# gk_midi_board_v2_5.net
KiCad netlist of a schematic drawn in EAGLE
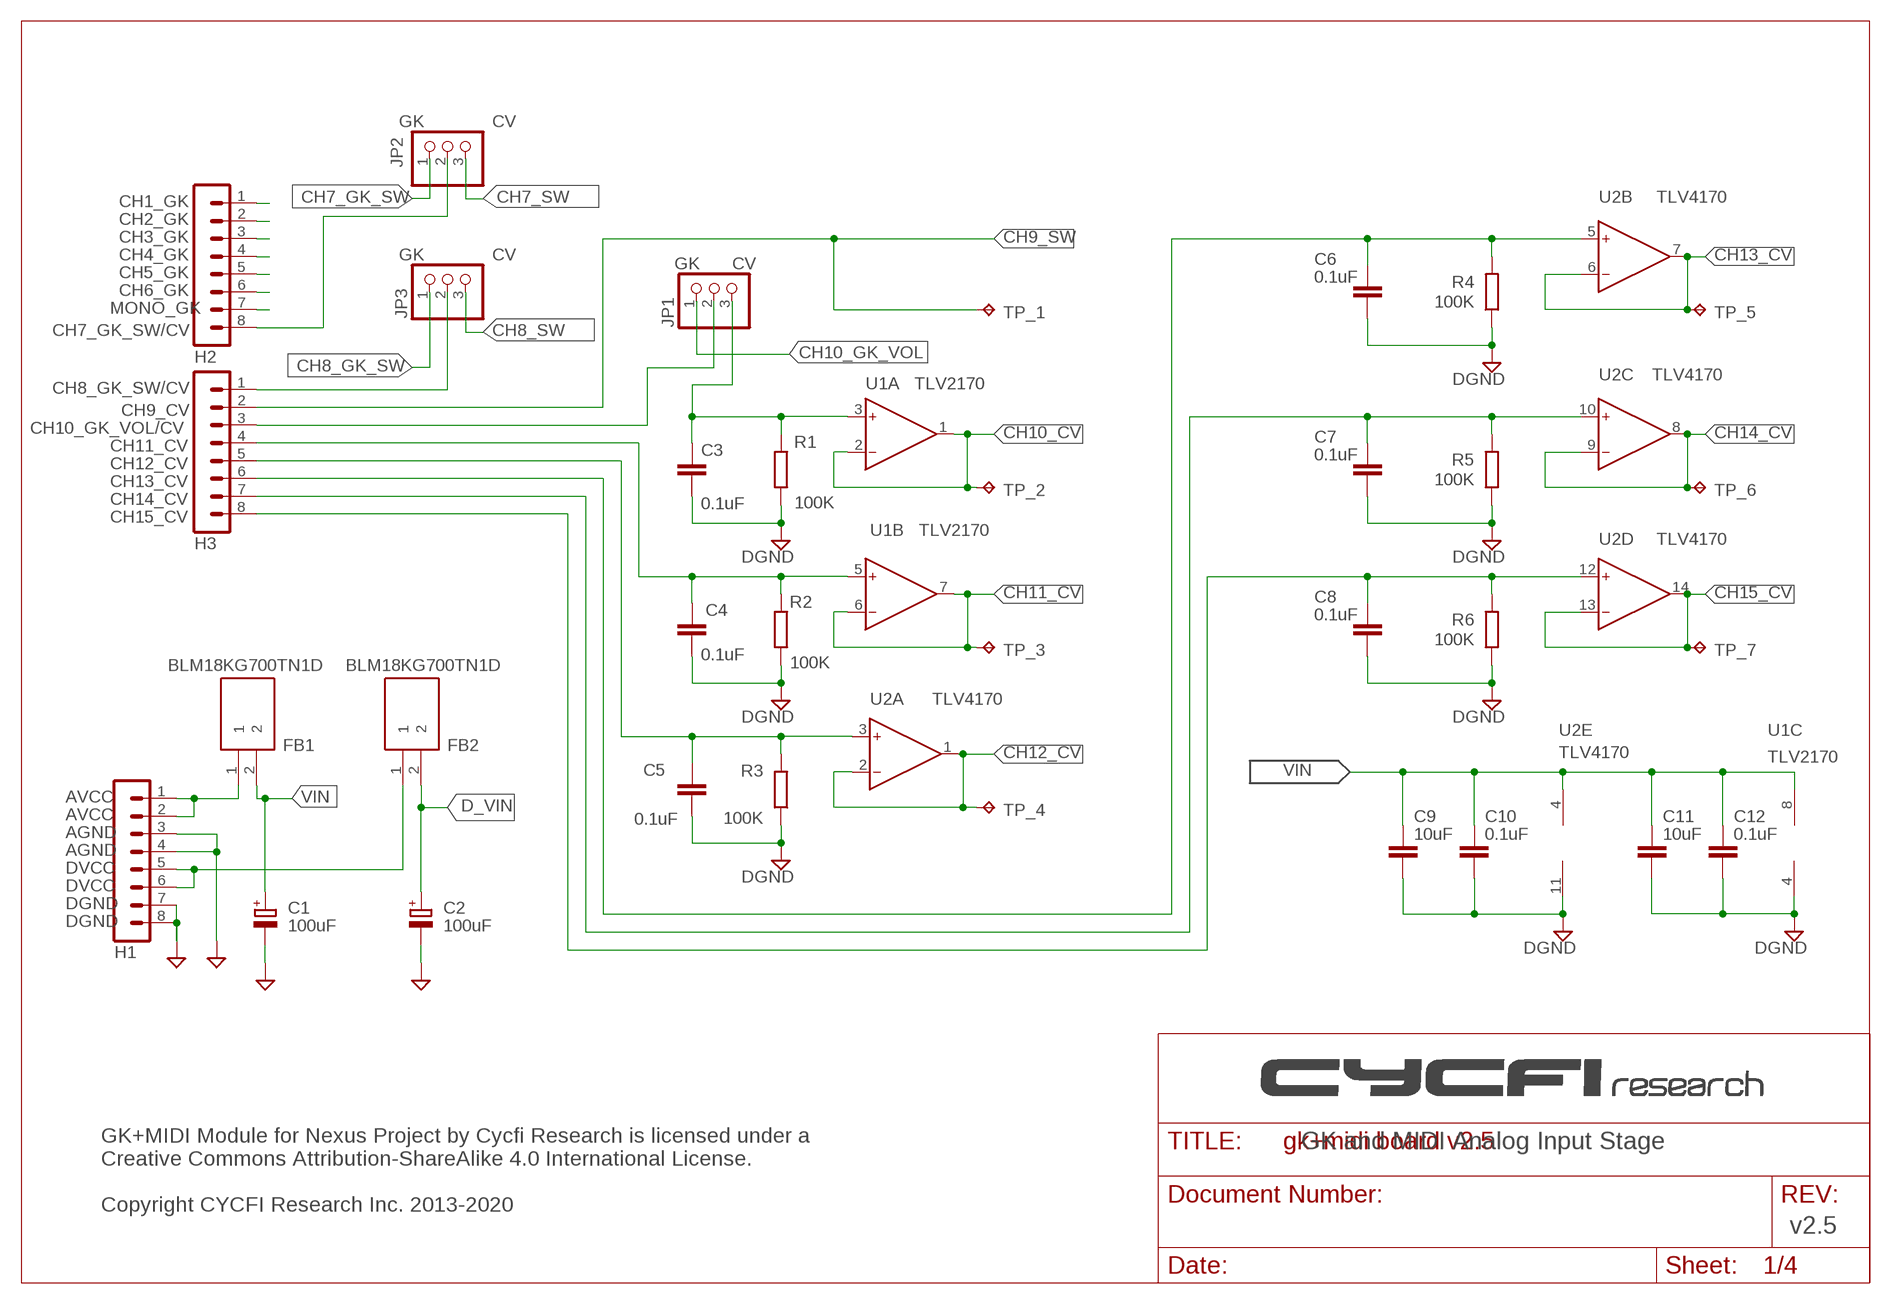
[diagram p0: schematic, sheet 1]
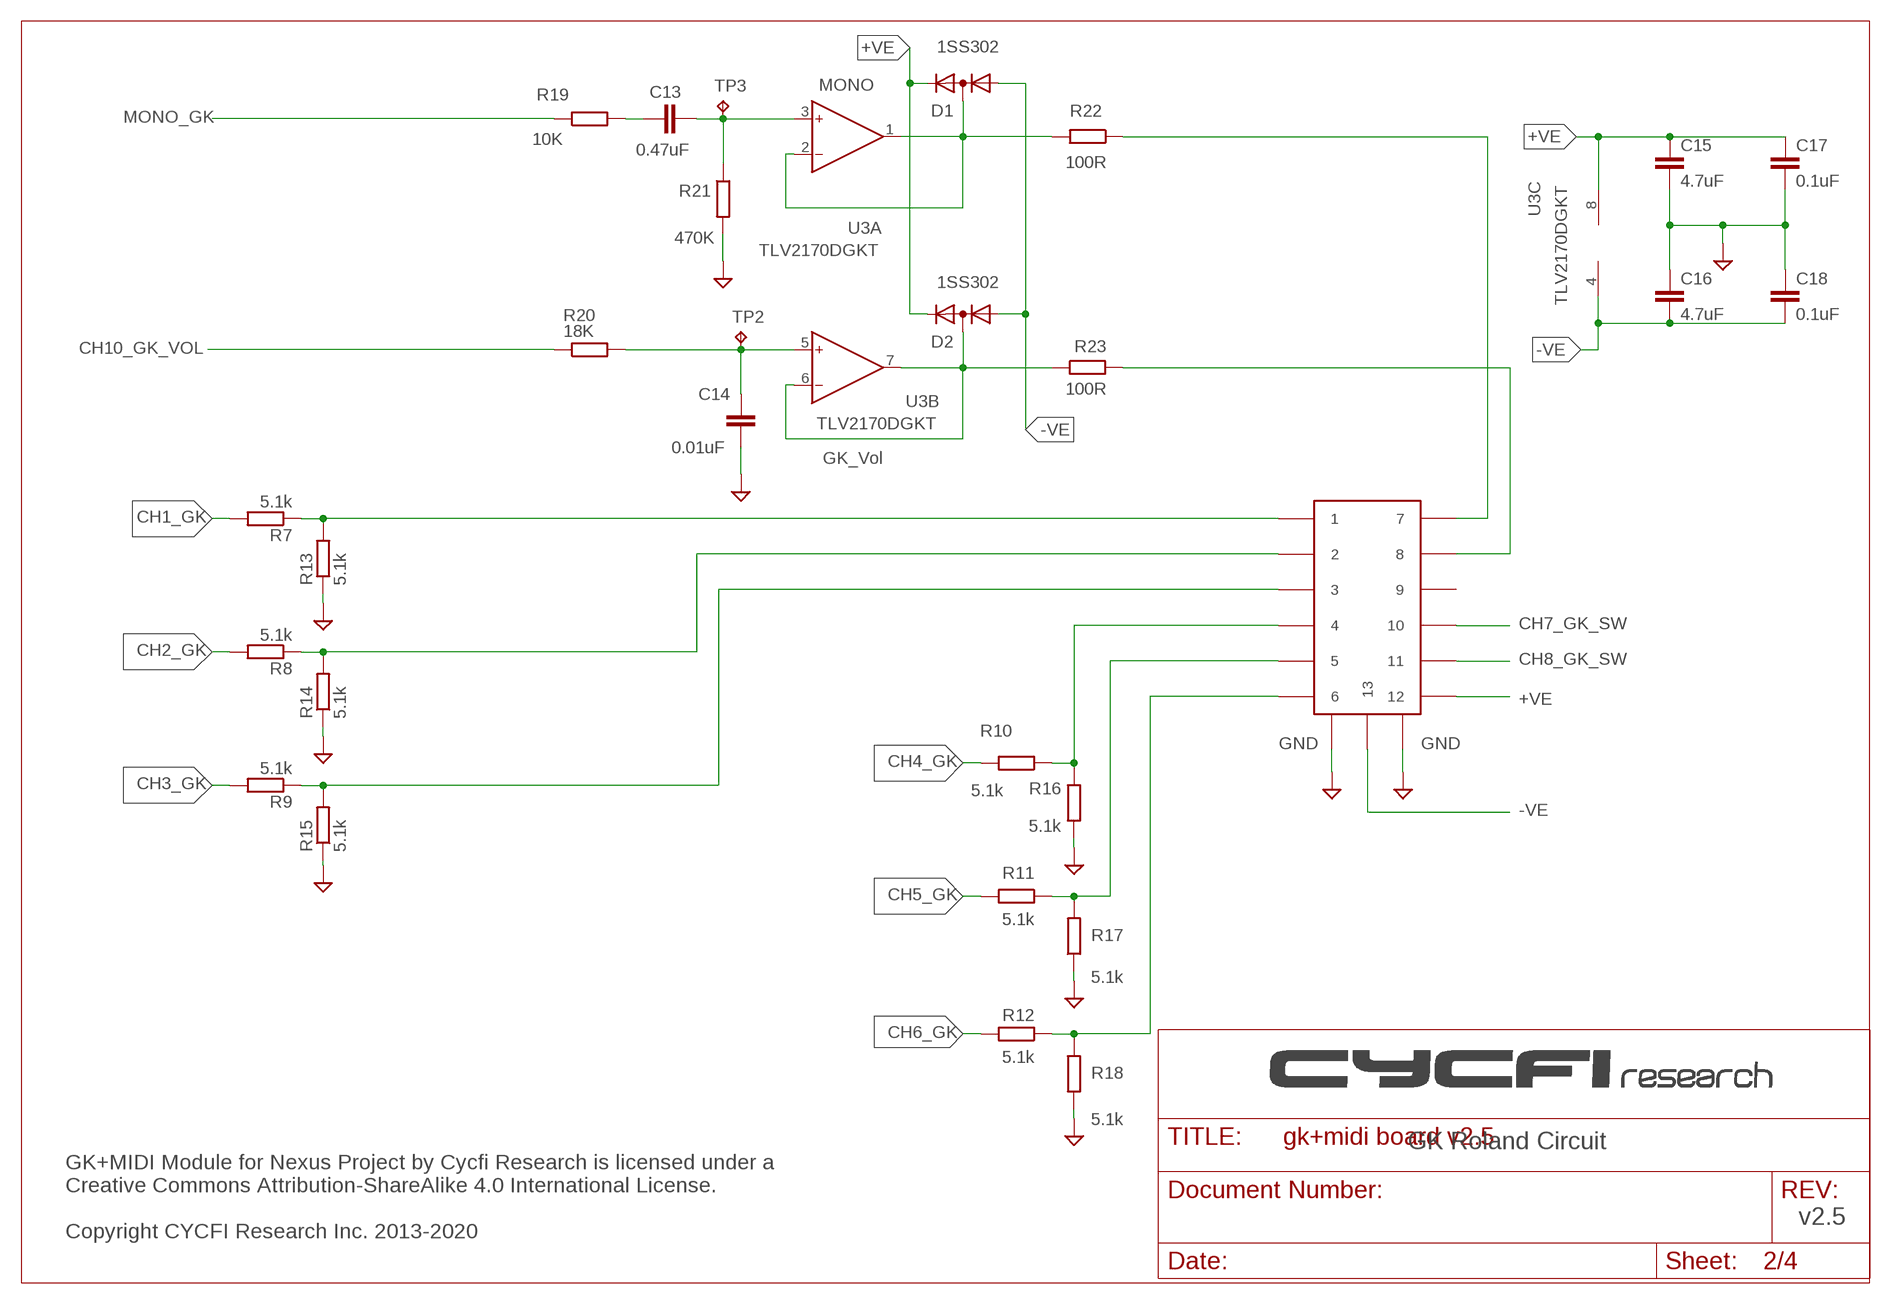
[diagram p1: schematic, sheet 2]
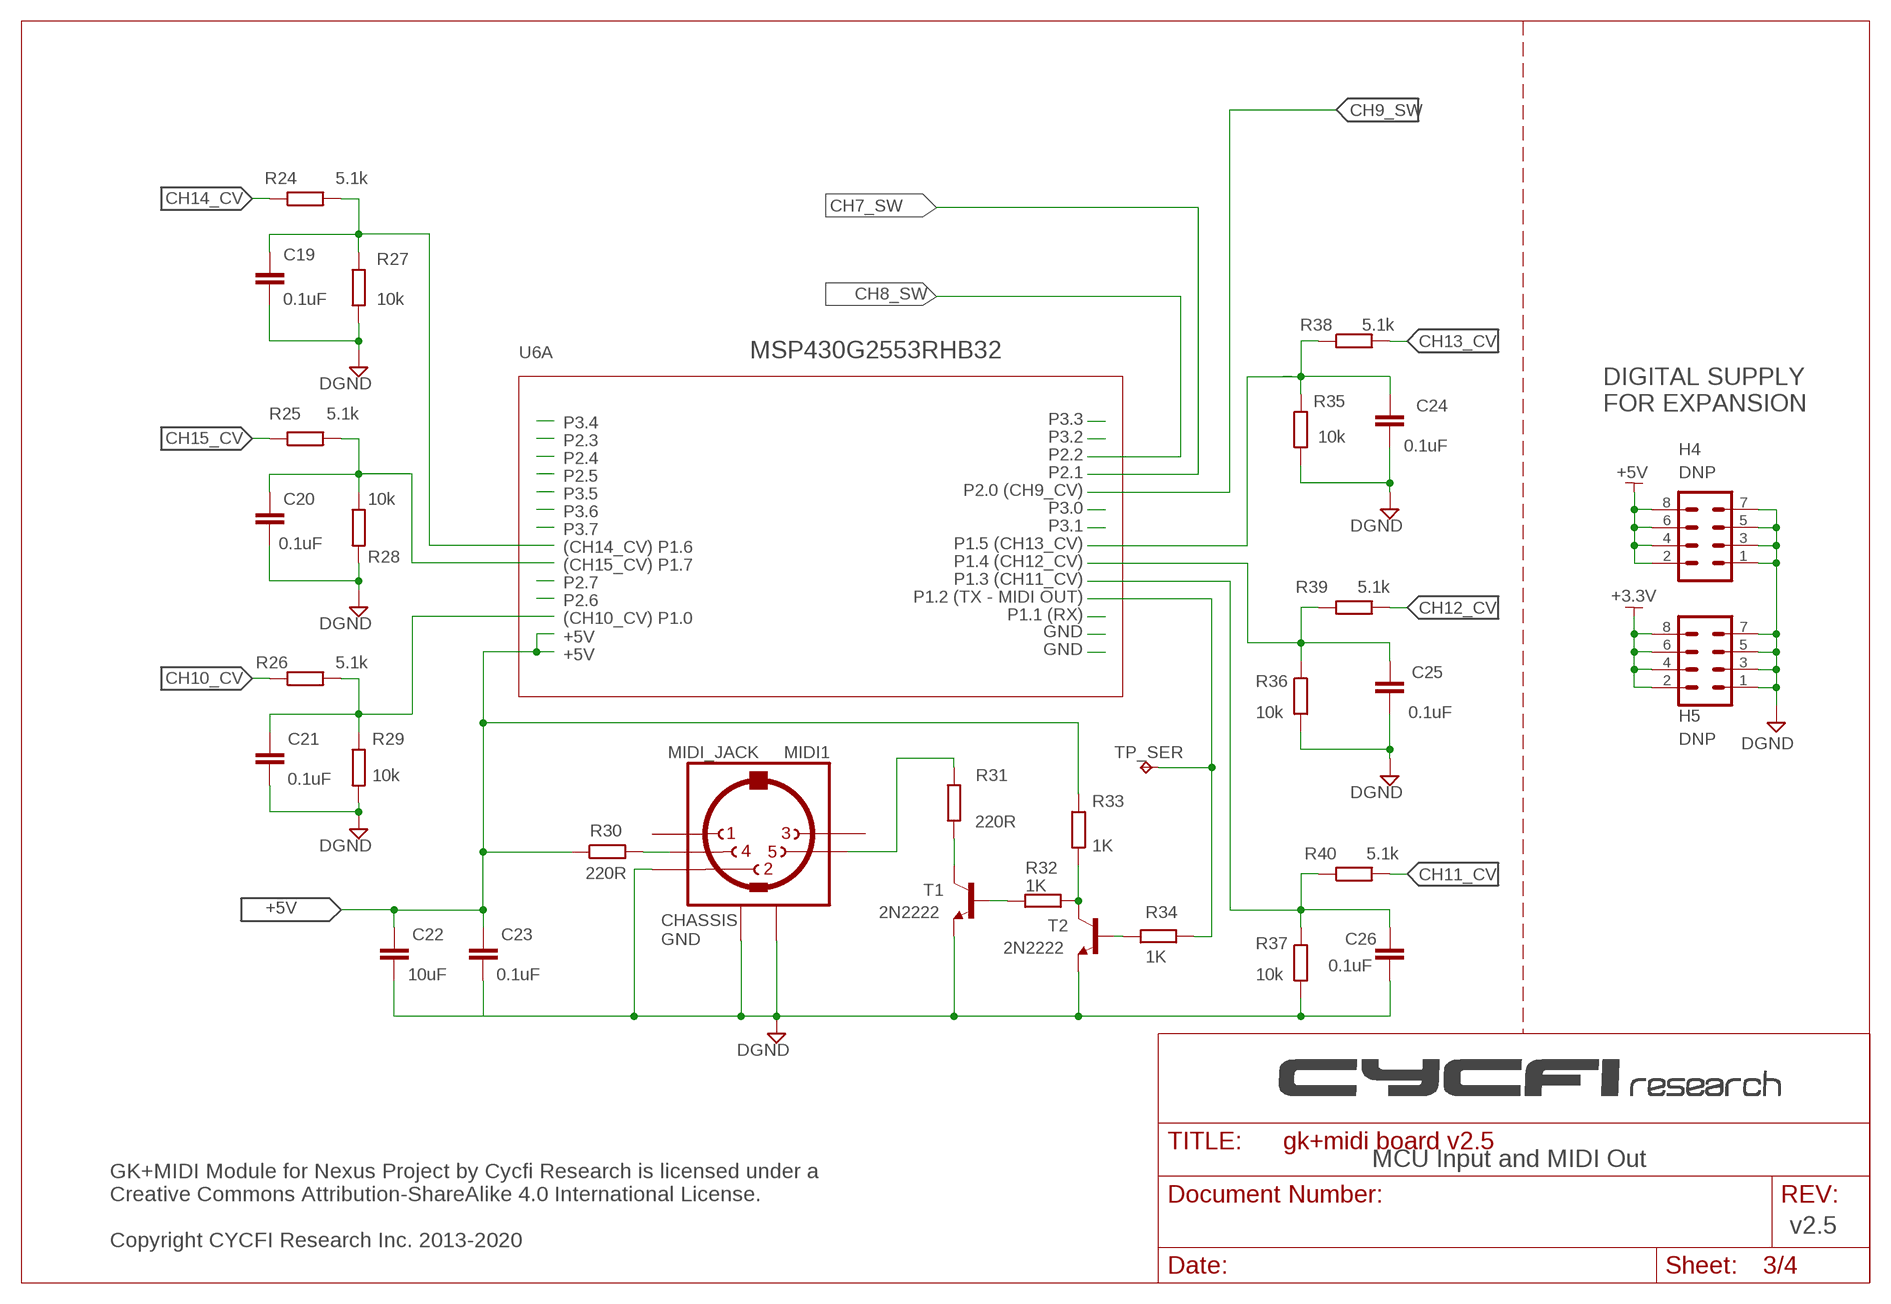
[diagram p2: schematic, sheet 3]
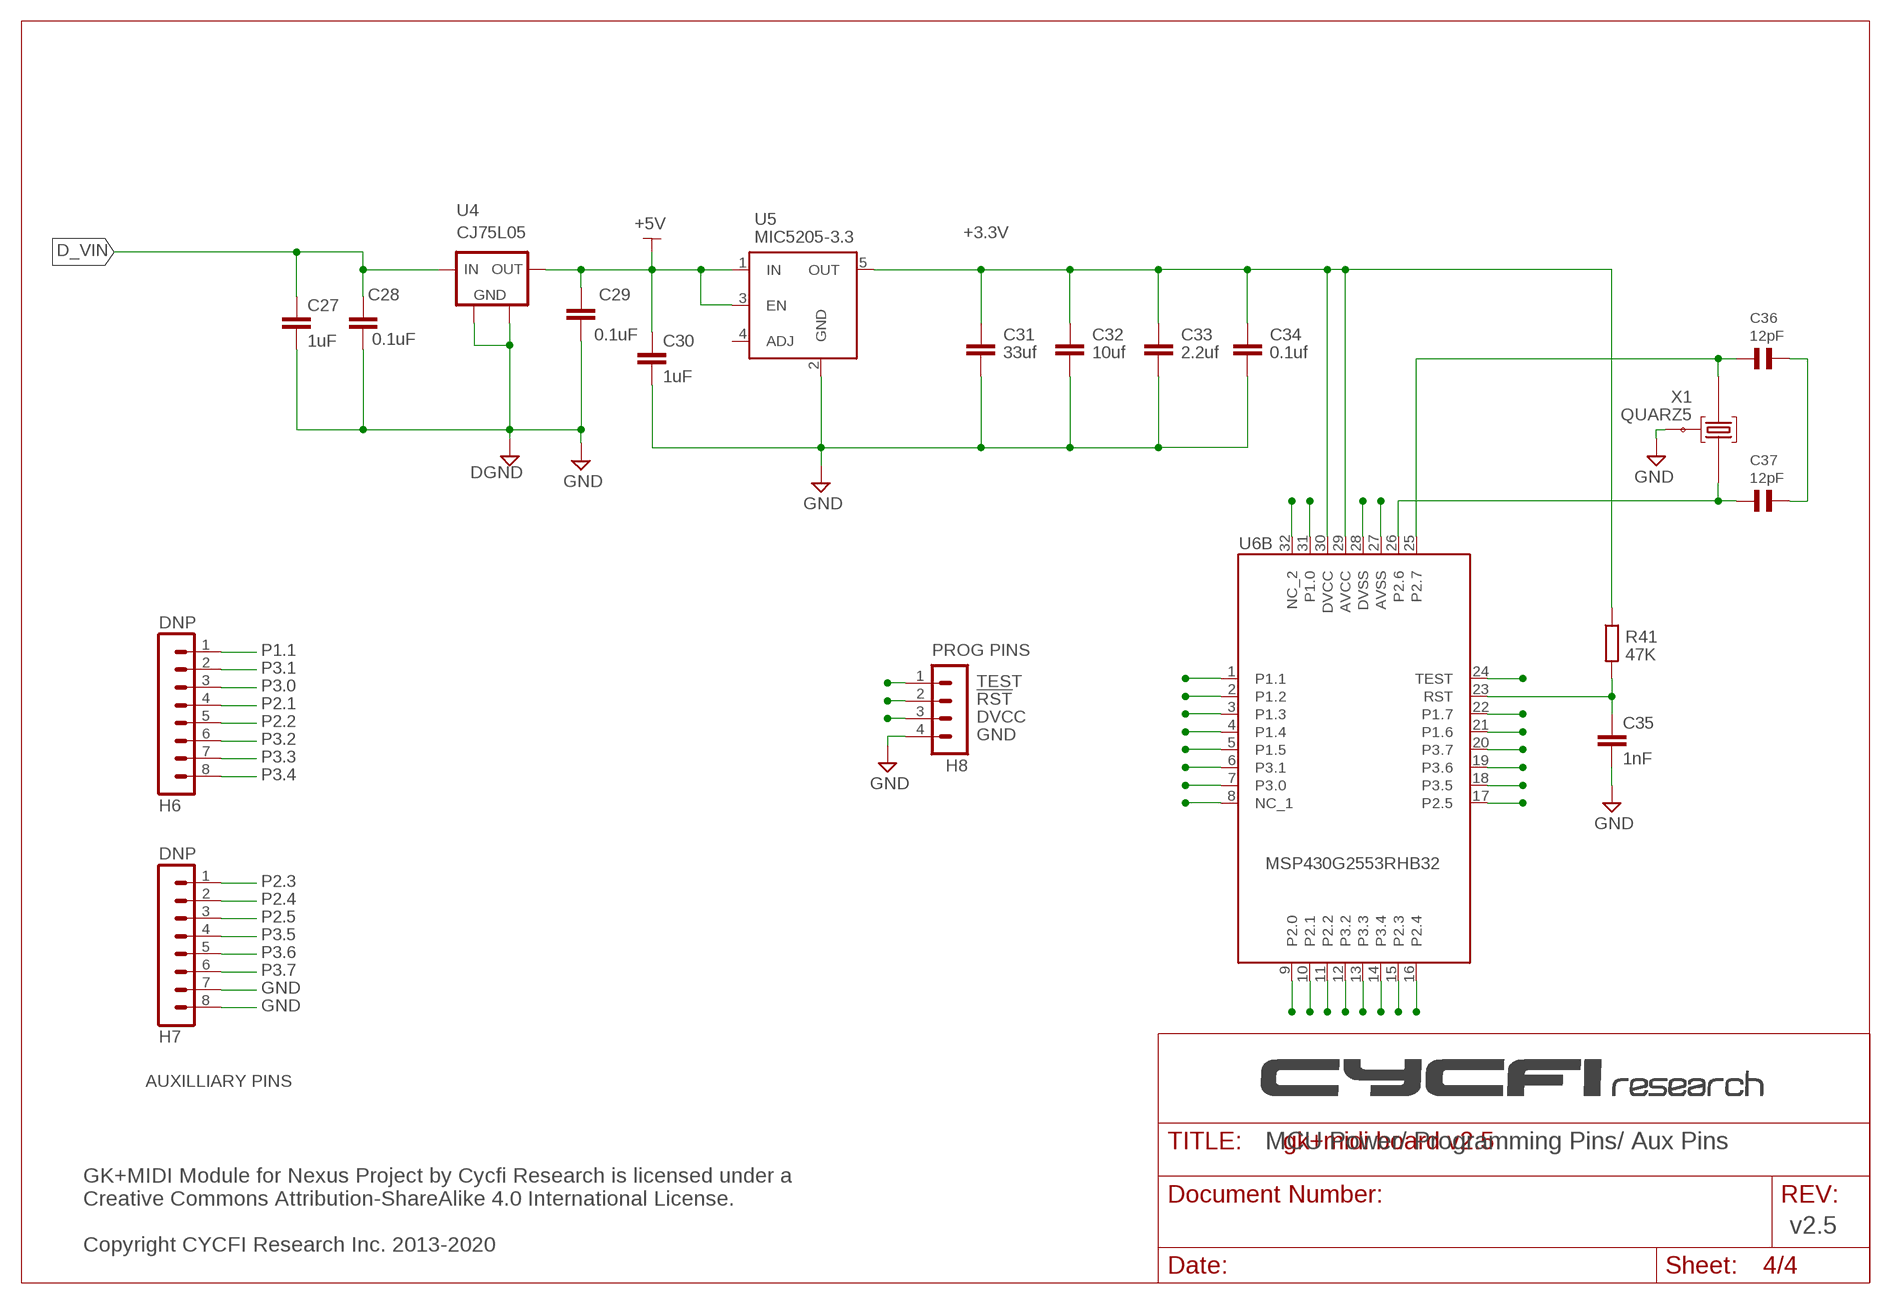
[diagram p3: schematic, sheet 4]

(export (version "E")
  (design (tool "Eeschema 10.0.6"))
  (components
    (comp (ref "C13")
      (value "0.47uF")
      (footprint "eagle-import:C0603")
      (libsource (lib "eagle-import") (part "C-EUC0603"))
    )
    (comp (ref "C14")
      (value "0.01uF")
      (footprint "eagle-import:C0402")
      (libsource (lib "eagle-import") (part "C-EUC0402"))
    )
    (comp (ref "C15")
      (value "4.7uF")
      (footprint "eagle-import:C0603")
      (libsource (lib "eagle-import") (part "C-EUC0603"))
    )
    (comp (ref "C16")
      (value "4.7uF")
      (footprint "eagle-import:C0603")
      (libsource (lib "eagle-import") (part "C-EUC0603"))
    )
    (comp (ref "C17")
      (value "0.1uF")
      (footprint "eagle-import:C0402")
      (libsource (lib "eagle-import") (part "C-EUC0402"))
    )
    (comp (ref "C18")
      (value "0.1uF")
      (footprint "eagle-import:C0402")
      (libsource (lib "eagle-import") (part "C-EUC0402"))
    )
    (comp (ref "D1")
      (value "1SS302")
      (footprint "eagle-import:SC70-3")
      (libsource (lib "eagle-import") (part "1SS302"))
    )
    (comp (ref "D2")
      (value "1SS302")
      (footprint "eagle-import:SC70-3")
      (libsource (lib "eagle-import") (part "1SS302"))
    )
    (comp (ref "R7")
      (value "5.1k")
      (footprint "eagle-import:R0402")
      (libsource (lib "eagle-import") (part "R-EU_R0402"))
    )
    (comp (ref "R8")
      (value "5.1k")
      (footprint "eagle-import:R0402")
      (libsource (lib "eagle-import") (part "R-EU_R0402"))
    )
    (comp (ref "R9")
      (value "5.1k")
      (footprint "eagle-import:R0402")
      (libsource (lib "eagle-import") (part "R-EU_R0402"))
    )
    (comp (ref "R10")
      (value "5.1k")
      (footprint "eagle-import:R0402")
      (libsource (lib "eagle-import") (part "R-EU_R0402"))
    )
    (comp (ref "R11")
      (value "5.1k")
      (footprint "eagle-import:R0402")
      (libsource (lib "eagle-import") (part "R-EU_R0402"))
    )
    (comp (ref "R12")
      (value "5.1k")
      (footprint "eagle-import:R0402")
      (libsource (lib "eagle-import") (part "R-EU_R0402"))
    )
    (comp (ref "R13")
      (value "5.1k")
      (footprint "eagle-import:R0402")
      (libsource (lib "eagle-import") (part "R-EU_R0402"))
    )
    (comp (ref "R14")
      (value "5.1k")
      (footprint "eagle-import:R0402")
      (libsource (lib "eagle-import") (part "R-EU_R0402"))
    )
    (comp (ref "R15")
      (value "5.1k")
      (footprint "eagle-import:R0402")
      (libsource (lib "eagle-import") (part "R-EU_R0402"))
    )
    (comp (ref "R16")
      (value "5.1k")
      (footprint "eagle-import:R0402")
      (libsource (lib "eagle-import") (part "R-EU_R0402"))
    )
    (comp (ref "R17")
      (value "5.1k")
      (footprint "eagle-import:R0402")
      (libsource (lib "eagle-import") (part "R-EU_R0402"))
    )
    (comp (ref "R18")
      (value "5.1k")
      (footprint "eagle-import:R0402")
      (libsource (lib "eagle-import") (part "R-EU_R0402"))
    )
    (comp (ref "R19")
      (value "10K")
      (footprint "eagle-import:R0402")
      (libsource (lib "eagle-import") (part "R-EU_R0402"))
    )
    (comp (ref "R20")
      (value "18K")
      (footprint "eagle-import:R0402")
      (libsource (lib "eagle-import") (part "R-EU_R0402"))
    )
    (comp (ref "R21")
      (value "470K")
      (footprint "eagle-import:R0402")
      (libsource (lib "eagle-import") (part "R-EU_R0402"))
    )
    (comp (ref "R22")
      (value "100R")
      (footprint "eagle-import:R0402")
      (libsource (lib "eagle-import") (part "R-EU_R0402"))
    )
    (comp (ref "R23")
      (value "100R")
      (footprint "eagle-import:R0402")
      (libsource (lib "eagle-import") (part "R-EU_R0402"))
    )
    (comp (ref "TP2")
      (value "TPB1,27")
      (footprint "eagle-import:B1,27")
      (libsource (lib "eagle-import") (part "TPB1,27"))
    )
    (comp (ref "TP3")
      (value "TPB1,27")
      (footprint "eagle-import:B1,27")
      (libsource (lib "eagle-import") (part "TPB1,27"))
    )
    (comp (ref "U$1")
      (value "13P_MIDI_2")
      (footprint "eagle-import:13P-MIDI-2")
      (libsource (lib "eagle-import") (part "13P_MIDI_2"))
    )
    (comp (ref "U3")
      (value "TLV2170DGKT")
      (footprint "eagle-import:MSOP8")
      (libsource (lib "eagle-import") (part "TLV2170DGKT"))
    )
    (comp (ref "C19")
      (value "0.1uF")
      (footprint "eagle-import:C0603")
      (libsource (lib "eagle-import") (part "C-EUC0603"))
    )
    (comp (ref "C20")
      (value "0.1uF")
      (footprint "eagle-import:C0603")
      (libsource (lib "eagle-import") (part "C-EUC0603"))
    )
    (comp (ref "C21")
      (value "0.1uF")
      (footprint "eagle-import:C0603")
      (libsource (lib "eagle-import") (part "C-EUC0603"))
    )
    (comp (ref "C22")
      (value "10uF")
      (footprint "eagle-import:C0805")
      (libsource (lib "eagle-import") (part "C-EUC0805"))
    )
    (comp (ref "C23")
      (value "0.1uF")
      (footprint "eagle-import:C0603")
      (libsource (lib "eagle-import") (part "C-EUC0603"))
    )
    (comp (ref "C24")
      (value "0.1uF")
      (footprint "eagle-import:C0603")
      (libsource (lib "eagle-import") (part "C-EUC0603"))
    )
    (comp (ref "C25")
      (value "0.1uF")
      (footprint "eagle-import:C0603")
      (libsource (lib "eagle-import") (part "C-EUC0603"))
    )
    (comp (ref "C26")
      (value "0.1uF")
      (footprint "eagle-import:C0603")
      (libsource (lib "eagle-import") (part "C-EUC0603"))
    )
    (comp (ref "H4")
      (value "DNP")
      (footprint "eagle-import:MA04-2")
      (libsource (lib "eagle-import") (part "MA04-2"))
    )
    (comp (ref "H5")
      (value "DNP")
      (footprint "eagle-import:MA04-2")
      (libsource (lib "eagle-import") (part "MA04-2"))
    )
    (comp (ref "MIDI1")
      (value "MIDI_JACK")
      (footprint "eagle-import:MIDI_JACK")
      (libsource (lib "eagle-import") (part "MIDI_JACK"))
    )
    (comp (ref "R24")
      (value "5.1k")
      (footprint "eagle-import:R0402")
      (libsource (lib "eagle-import") (part "R-EU_R0402"))
    )
    (comp (ref "R25")
      (value "5.1k")
      (footprint "eagle-import:R0402")
      (libsource (lib "eagle-import") (part "R-EU_R0402"))
    )
    (comp (ref "R26")
      (value "5.1k")
      (footprint "eagle-import:R0402")
      (libsource (lib "eagle-import") (part "R-EU_R0402"))
    )
    (comp (ref "R27")
      (value "10k")
      (footprint "eagle-import:R0402")
      (libsource (lib "eagle-import") (part "R-EU_R0402"))
    )
    (comp (ref "R28")
      (value "10k")
      (footprint "eagle-import:R0402")
      (libsource (lib "eagle-import") (part "R-EU_R0402"))
    )
    (comp (ref "R29")
      (value "10k")
      (footprint "eagle-import:R0402")
      (libsource (lib "eagle-import") (part "R-EU_R0402"))
    )
    (comp (ref "R30")
      (value "220R")
      (footprint "eagle-import:R0603")
      (libsource (lib "eagle-import") (part "R-EU_R0603"))
    )
    (comp (ref "R31")
      (value "220R")
      (footprint "eagle-import:R0603")
      (libsource (lib "eagle-import") (part "R-EU_R0603"))
    )
    (comp (ref "R32")
      (value "1K")
      (footprint "eagle-import:R0402")
      (libsource (lib "eagle-import") (part "R-EU_R0402"))
    )
    (comp (ref "R33")
      (value "1K")
      (footprint "eagle-import:R0402")
      (libsource (lib "eagle-import") (part "R-EU_R0402"))
    )
    (comp (ref "R34")
      (value "1K")
      (footprint "eagle-import:R0402")
      (libsource (lib "eagle-import") (part "R-EU_R0402"))
    )
    (comp (ref "R35")
      (value "10k")
      (footprint "eagle-import:R0402")
      (libsource (lib "eagle-import") (part "R-EU_R0402"))
    )
    (comp (ref "R36")
      (value "10k")
      (footprint "eagle-import:R0402")
      (libsource (lib "eagle-import") (part "R-EU_R0402"))
    )
    (comp (ref "R37")
      (value "10k")
      (footprint "eagle-import:R0402")
      (libsource (lib "eagle-import") (part "R-EU_R0402"))
    )
    (comp (ref "R38")
      (value "5.1k")
      (footprint "eagle-import:R0402")
      (libsource (lib "eagle-import") (part "R-EU_R0402"))
    )
    (comp (ref "R39")
      (value "5.1k")
      (footprint "eagle-import:R0402")
      (libsource (lib "eagle-import") (part "R-EU_R0402"))
    )
    (comp (ref "R40")
      (value "5.1k")
      (footprint "eagle-import:R0402")
      (libsource (lib "eagle-import") (part "R-EU_R0402"))
    )
    (comp (ref "T1")
      (value "2N2222")
      (footprint "eagle-import:SOT23-3")
      (libsource (lib "eagle-import") (part "TRAN-MMBT2222A"))
    )
    (comp (ref "T2")
      (value "2N2222")
      (footprint "eagle-import:SOT23-3")
      (libsource (lib "eagle-import") (part "TRAN-MMBT2222A"))
    )
    (comp (ref "TP_SER")
      (value "TPB1,27")
      (footprint "eagle-import:B1,27")
      (libsource (lib "eagle-import") (part "TPB1,27"))
    )
    (comp (ref "C27")
      (value "1uF")
      (footprint "eagle-import:C0402")
      (libsource (lib "eagle-import") (part "C-EUC0402"))
    )
    (comp (ref "C28")
      (value "0.1uF")
      (footprint "eagle-import:C0603")
      (libsource (lib "eagle-import") (part "C-EUC0603"))
    )
    (comp (ref "C29")
      (value "0.1uF")
      (footprint "eagle-import:C0603")
      (libsource (lib "eagle-import") (part "C-EUC0603"))
    )
    (comp (ref "C30")
      (value "1uF")
      (footprint "eagle-import:C0402")
      (libsource (lib "eagle-import") (part "C-EUC0402"))
    )
    (comp (ref "C31")
      (value "33uf")
      (footprint "eagle-import:C0805")
      (libsource (lib "eagle-import") (part "C-EUC0805"))
    )
    (comp (ref "C32")
      (value "10uf")
      (footprint "eagle-import:C0805")
      (libsource (lib "eagle-import") (part "C-EUC0805"))
    )
    (comp (ref "C33")
      (value "2.2uf")
      (footprint "eagle-import:C0805")
      (libsource (lib "eagle-import") (part "C-EUC0805"))
    )
    (comp (ref "C34")
      (value "0.1uf")
      (footprint "eagle-import:C0603")
      (libsource (lib "eagle-import") (part "C-EUC0603"))
    )
    (comp (ref "C35")
      (value "1nF")
      (footprint "eagle-import:C0402")
      (libsource (lib "eagle-import") (part "C-EUC0402"))
    )
    (comp (ref "C36")
      (value "12pF")
      (footprint "eagle-import:0603")
      (libsource (lib "eagle-import") (part "C_SMD0603"))
    )
    (comp (ref "C37")
      (value "12pF")
      (footprint "eagle-import:0603")
      (libsource (lib "eagle-import") (part "C_SMD0603"))
    )
    (comp (ref "H6")
      (value "DNP")
      (footprint "eagle-import:MA08-1")
      (libsource (lib "eagle-import") (part "MA08-1"))
    )
    (comp (ref "H7")
      (value "DNP")
      (footprint "eagle-import:MA08-1")
      (libsource (lib "eagle-import") (part "MA08-1"))
    )
    (comp (ref "H8")
      (value "MA04-1")
      (footprint "eagle-import:MA04-1")
      (libsource (lib "eagle-import") (part "MA04-1"))
    )
    (comp (ref "R41")
      (value "47K")
      (footprint "eagle-import:R0402")
      (libsource (lib "eagle-import") (part "R-EU_R0402"))
    )
    (comp (ref "U4")
      (value "L78LXX")
      (footprint "eagle-import:SOT89")
      (libsource (lib "eagle-import") (part "L78LXX"))
    )
    (comp (ref "U5")
      (value "MIC5205-3.3")
      (footprint "eagle-import:SOT23-5")
      (fields (field (name "MF") "ALTERA CORPORATION") (field (name "MPN") "MIC5219BM5 TR"))
      (libsource (lib "eagle-import") (part "MIC5219BM5"))
    )
    (comp (ref "U6B")
      (value "MSP430G2553RHB32")
      (footprint "eagle-import:QFN32")
      (libsource (lib "eagle-import") (part "MSP430G2553RHB32"))
    )
    (comp (ref "X1")
      (value "QUARZ5")
      (footprint "eagle-import:QUARZ5")
      (libsource (lib "eagle-import") (part "QUARZ5"))
    )
    (comp (ref "C1")
      (value "100uF")
      (footprint "eagle-import:153CLV-0505")
      (libsource (lib "eagle-import") (part "CPOL-EU153CLV-0505"))
    )
    (comp (ref "C2")
      (value "100uF")
      (footprint "eagle-import:153CLV-0505")
      (libsource (lib "eagle-import") (part "CPOL-EU153CLV-0505"))
    )
    (comp (ref "C3")
      (value "0.1uF")
      (footprint "eagle-import:C0603")
      (libsource (lib "eagle-import") (part "C-EUC0603"))
    )
    (comp (ref "C4")
      (value "0.1uF")
      (footprint "eagle-import:C0603")
      (libsource (lib "eagle-import") (part "C-EUC0603"))
    )
    (comp (ref "C5")
      (value "0.1uF")
      (footprint "eagle-import:C0603")
      (libsource (lib "eagle-import") (part "C-EUC0603"))
    )
    (comp (ref "C6")
      (value "0.1uF")
      (footprint "eagle-import:C0603")
      (libsource (lib "eagle-import") (part "C-EUC0603"))
    )
    (comp (ref "C7")
      (value "0.1uF")
      (footprint "eagle-import:C0603")
      (libsource (lib "eagle-import") (part "C-EUC0603"))
    )
    (comp (ref "C8")
      (value "0.1uF")
      (footprint "eagle-import:C0603")
      (libsource (lib "eagle-import") (part "C-EUC0603"))
    )
    (comp (ref "C9")
      (value "10uF")
      (footprint "eagle-import:C0805")
      (libsource (lib "eagle-import") (part "C-EUC0805"))
    )
    (comp (ref "C10")
      (value "0.1uF")
      (footprint "eagle-import:C0603")
      (libsource (lib "eagle-import") (part "C-EUC0603"))
    )
    (comp (ref "C11")
      (value "10uF")
      (footprint "eagle-import:C0805")
      (libsource (lib "eagle-import") (part "C-EUC0805"))
    )
    (comp (ref "C12")
      (value "0.1uF")
      (footprint "eagle-import:C0603")
      (libsource (lib "eagle-import") (part "C-EUC0603"))
    )
    (comp (ref "FB1")
      (value "BLM18KG700TN1D")
      (footprint "eagle-import:BEADC1608X75N")
      (fields (field (name "MOUSER_PART_NUMBER") "81-BLM18KG700TN1D"))
      (libsource (lib "eagle-import") (part "BLM18KG700TN1D"))
    )
    (comp (ref "FB2")
      (value "BLM18KG700TN1D")
      (footprint "eagle-import:BEADC1608X75N")
      (description "BLM18_N1D Series EMI Suppression Filter 70+/-25% at 100MHz 3.5A @85")
      (fields
        (field (name "MOUSER_PART_NUMBER") "81-BLM18KG700TN1D")
        (field (name "HEIGHT") "0.75mm")
        (field (name "MANUFACTURER_NAME") "Murata Electronics")
        (field (name "MANUFACTURER_PART_NUMBER") "BLM18KG700TN1D")
        (field (name "MOUSER_PART_NUMBER_1") "81-BLM18KG700TN1D")
        (field (name "MOUSER_PRICE-STOCK") "https://www.mouser.com/Search/Refine.aspx?Keyword=81-BLM18KG700TN1D")
      )
      (libsource (lib "eagle-import") (part "BLM18KG700TN1D"))
    )
    (comp (ref "H1")
      (value "MA08-1")
      (footprint "eagle-import:MA08-1")
      (libsource (lib "eagle-import") (part "MA08-1"))
    )
    (comp (ref "H2")
      (value "MA08-1")
      (footprint "eagle-import:MA08-1")
      (libsource (lib "eagle-import") (part "MA08-1"))
    )
    (comp (ref "H3")
      (value "MA08-1")
      (footprint "eagle-import:MA08-1")
      (libsource (lib "eagle-import") (part "MA08-1"))
    )
    (comp (ref "JP1")
      (value "PINHD-1X03_2.00")
      (footprint "eagle-import:1X03M")
      (libsource (lib "eagle-import") (part "PINHD-1X03_2.00"))
    )
    (comp (ref "JP2")
      (value "PINHD-1X03_2.00")
      (footprint "eagle-import:1X03M")
      (libsource (lib "eagle-import") (part "PINHD-1X03_2.00"))
    )
    (comp (ref "JP3")
      (value "PINHD-1X03_2.00")
      (footprint "eagle-import:1X03M")
      (libsource (lib "eagle-import") (part "PINHD-1X03_2.00"))
    )
    (comp (ref "R1")
      (value "100K")
      (footprint "eagle-import:R0402")
      (libsource (lib "eagle-import") (part "R-EU_R0402"))
    )
    (comp (ref "R2")
      (value "100K")
      (footprint "eagle-import:R0402")
      (libsource (lib "eagle-import") (part "R-EU_R0402"))
    )
    (comp (ref "R3")
      (value "100K")
      (footprint "eagle-import:R0402")
      (libsource (lib "eagle-import") (part "R-EU_R0402"))
    )
    (comp (ref "R4")
      (value "100K")
      (footprint "eagle-import:R0402")
      (libsource (lib "eagle-import") (part "R-EU_R0402"))
    )
    (comp (ref "R5")
      (value "100K")
      (footprint "eagle-import:R0402")
      (libsource (lib "eagle-import") (part "R-EU_R0402"))
    )
    (comp (ref "R6")
      (value "100K")
      (footprint "eagle-import:R0402")
      (libsource (lib "eagle-import") (part "R-EU_R0402"))
    )
    (comp (ref "TP_1")
      (value "TPB1,27")
      (footprint "eagle-import:B1,27")
      (libsource (lib "eagle-import") (part "TPB1,27"))
    )
    (comp (ref "TP_2")
      (value "TPB1,27")
      (footprint "eagle-import:B1,27")
      (libsource (lib "eagle-import") (part "TPB1,27"))
    )
    (comp (ref "TP_3")
      (value "TPB1,27")
      (footprint "eagle-import:B1,27")
      (libsource (lib "eagle-import") (part "TPB1,27"))
    )
    (comp (ref "TP_4")
      (value "TPB1,27")
      (footprint "eagle-import:B1,27")
      (libsource (lib "eagle-import") (part "TPB1,27"))
    )
    (comp (ref "TP_5")
      (value "TPB1,27")
      (footprint "eagle-import:B1,27")
      (libsource (lib "eagle-import") (part "TPB1,27"))
    )
    (comp (ref "TP_6")
      (value "TPB1,27")
      (footprint "eagle-import:B1,27")
      (libsource (lib "eagle-import") (part "TPB1,27"))
    )
    (comp (ref "TP_7")
      (value "TPB1,27")
      (footprint "eagle-import:B1,27")
      (libsource (lib "eagle-import") (part "TPB1,27"))
    )
    (comp (ref "U1")
      (value "TLV2170DGKT")
      (footprint "eagle-import:MSOP8")
      (libsource (lib "eagle-import") (part "TLV2170DGKT"))
    )
    (comp (ref "U2")
      (value "LMV324")
      (footprint "eagle-import:SSOP-14")
      (libsource (lib "eagle-import") (part "LMV324"))
    )
  )
  (nets
    (net (code "1") (name "+3.3V") (class "Default")
      (node (ref "C31") (pin "1") (pinfunction "1_1") (pintype "passive"))
      (node (ref "C32") (pin "1") (pinfunction "1_1") (pintype "passive"))
      (node (ref "C33") (pin "1") (pinfunction "1_1") (pintype "passive"))
      (node (ref "C34") (pin "1") (pinfunction "1_1") (pintype "passive"))
      (node (ref "H5") (pin "2") (pinfunction "2_2") (pintype "passive"))
      (node (ref "H5") (pin "4") (pinfunction "4_4") (pintype "passive"))
      (node (ref "H5") (pin "6") (pinfunction "6_6") (pintype "passive"))
      (node (ref "H5") (pin "8") (pinfunction "8_8") (pintype "passive"))
      (node (ref "H8") (pin "3") (pinfunction "3_3") (pintype "passive"))
      (node (ref "R41") (pin "1") (pinfunction "1_1") (pintype "passive"))
      (node (ref "U5") (pin "5") (pinfunction "OUT_5") (pintype "output"))
      (node (ref "U6B") (pin "29") (pinfunction "AVCC_29") (pintype "bidirectional"))
      (node (ref "U6B") (pin "30") (pinfunction "DVCC_30") (pintype "bidirectional"))
    )
    (net (code "2") (name "+5V") (class "Default")
      (node (ref "C22") (pin "1") (pinfunction "1_1") (pintype "passive"))
      (node (ref "C23") (pin "1") (pinfunction "1_1") (pintype "passive"))
      (node (ref "C29") (pin "1") (pinfunction "1_1") (pintype "passive"))
      (node (ref "C30") (pin "1") (pinfunction "1_1") (pintype "passive"))
      (node (ref "H4") (pin "2") (pinfunction "2_2") (pintype "passive"))
      (node (ref "H4") (pin "4") (pinfunction "4_4") (pintype "passive"))
      (node (ref "H4") (pin "6") (pinfunction "6_6") (pintype "passive"))
      (node (ref "H4") (pin "8") (pinfunction "8_8") (pintype "passive"))
      (node (ref "R30") (pin "1") (pinfunction "1_1") (pintype "passive"))
      (node (ref "R33") (pin "2") (pinfunction "2_2") (pintype "passive"))
      (node (ref "U4") (pin "1") (pinfunction "IN_1") (pintype "input"))
      (node (ref "U5") (pin "1") (pinfunction "IN_1") (pintype "input"))
      (node (ref "U5") (pin "3") (pinfunction "EN_3") (pintype "input"))
    )
    (net (code "3") (name "+VE") (class "Default")
      (node (ref "C15") (pin "1") (pinfunction "1_1") (pintype "passive"))
      (node (ref "C17") (pin "1") (pinfunction "1_1") (pintype "passive"))
      (node (ref "D1") (pin "2") (pinfunction "K_2") (pintype "passive"))
      (node (ref "D2") (pin "2") (pinfunction "K_2") (pintype "passive"))
      (node (ref "U$1") (pin "12") (pinfunction "12_12") (pintype "bidirectional"))
      (node (ref "U3") (pin "8") (pinfunction "V+_8") (pintype "power_in"))
    )
    (net (code "4") (name "-VE") (class "Default")
      (node (ref "C16") (pin "2") (pinfunction "2_2") (pintype "passive"))
      (node (ref "C18") (pin "2") (pinfunction "2_2") (pintype "passive"))
      (node (ref "D1") (pin "1") (pinfunction "A_1") (pintype "passive"))
      (node (ref "D2") (pin "1") (pinfunction "A_1") (pintype "passive"))
      (node (ref "U$1") (pin "13") (pinfunction "13_13") (pintype "bidirectional"))
      (node (ref "U3") (pin "4") (pinfunction "V-_4") (pintype "power_in"))
    )
    (net (code "5") (name "AVCC") (class "Default")
      (node (ref "FB1") (pin "1") (pinfunction "1_1") (pintype "bidirectional"))
      (node (ref "H1") (pin "1") (pinfunction "1_1") (pintype "passive"))
      (node (ref "H1") (pin "2") (pinfunction "2_2") (pintype "passive"))
    )
    (net (code "6") (name "CH1_GK") (class "Default")
      (node (ref "H2") (pin "1") (pinfunction "1_1") (pintype "passive"))
      (node (ref "R7") (pin "2") (pinfunction "2_2") (pintype "passive"))
    )
    (net (code "7") (name "CH2_GK") (class "Default")
      (node (ref "H2") (pin "2") (pinfunction "2_2") (pintype "passive"))
      (node (ref "R8") (pin "2") (pinfunction "2_2") (pintype "passive"))
    )
    (net (code "8") (name "CH3_GK") (class "Default")
      (node (ref "H2") (pin "3") (pinfunction "3_3") (pintype "passive"))
      (node (ref "R9") (pin "2") (pinfunction "2_2") (pintype "passive"))
    )
    (net (code "9") (name "CH4_GK") (class "Default")
      (node (ref "H2") (pin "4") (pinfunction "4_4") (pintype "passive"))
      (node (ref "R10") (pin "2") (pinfunction "2_2") (pintype "passive"))
    )
    (net (code "10") (name "CH5_GK") (class "Default")
      (node (ref "H2") (pin "5") (pinfunction "5_5") (pintype "passive"))
      (node (ref "R11") (pin "2") (pinfunction "2_2") (pintype "passive"))
    )
    (net (code "11") (name "CH6_GK") (class "Default")
      (node (ref "H2") (pin "6") (pinfunction "6_6") (pintype "passive"))
      (node (ref "R12") (pin "2") (pinfunction "2_2") (pintype "passive"))
    )
    (net (code "12") (name "CH7_GK_SW") (class "Default")
      (node (ref "JP2") (pin "1") (pinfunction "1_1") (pintype "passive"))
      (node (ref "U$1") (pin "10") (pinfunction "10_10") (pintype "bidirectional"))
    )
    (net (code "13") (name "CH7_SW") (class "Default")
      (node (ref "H6") (pin "4") (pinfunction "4_4") (pintype "passive"))
      (node (ref "JP2") (pin "3") (pinfunction "3_3") (pintype "passive"))
      (node (ref "U6B") (pin "10") (pinfunction "P2.1_10") (pintype "bidirectional"))
    )
    (net (code "14") (name "CH8_GK_SW") (class "Default")
      (node (ref "JP3") (pin "1") (pinfunction "1_1") (pintype "passive"))
      (node (ref "U$1") (pin "11") (pinfunction "11_11") (pintype "bidirectional"))
    )
    (net (code "15") (name "CH8_SW") (class "Default")
      (node (ref "H6") (pin "5") (pinfunction "5_5") (pintype "passive"))
      (node (ref "JP3") (pin "3") (pinfunction "3_3") (pintype "passive"))
      (node (ref "U6B") (pin "11") (pinfunction "P2.2_11") (pintype "bidirectional"))
    )
    (net (code "16") (name "CH9_SW") (class "Default")
      (node (ref "H3") (pin "2") (pinfunction "2_2") (pintype "passive"))
      (node (ref "TP_1") (pin "TP") (pinfunction "TP_TP") (pintype "input"))
      (node (ref "U6B") (pin "9") (pinfunction "P2.0_9") (pintype "bidirectional"))
    )
    (net (code "17") (name "CH10_CV") (class "Default")
      (node (ref "R26") (pin "1") (pinfunction "1_1") (pintype "passive"))
      (node (ref "TP_2") (pin "TP") (pinfunction "TP_TP") (pintype "input"))
      (node (ref "U1") (pin "1") (pinfunction "OUT_1") (pintype "output"))
      (node (ref "U1") (pin "2") (pinfunction "IN-_2") (pintype "input"))
    )
    (net (code "18") (name "CH10_GK_VOL") (class "Default")
      (node (ref "JP1") (pin "1") (pinfunction "1_1") (pintype "passive"))
      (node (ref "R20") (pin "1") (pinfunction "1_1") (pintype "passive"))
    )
    (net (code "19") (name "CH11_CV") (class "Default")
      (node (ref "R40") (pin "2") (pinfunction "2_2") (pintype "passive"))
      (node (ref "TP_3") (pin "TP") (pinfunction "TP_TP") (pintype "input"))
      (node (ref "U1") (pin "6") (pinfunction "IN-_6") (pintype "input"))
      (node (ref "U1") (pin "7") (pinfunction "OUT_7") (pintype "output"))
    )
    (net (code "20") (name "CH12_CV") (class "Default")
      (node (ref "R39") (pin "2") (pinfunction "2_2") (pintype "passive"))
      (node (ref "TP_4") (pin "TP") (pinfunction "TP_TP") (pintype "input"))
      (node (ref "U2") (pin "1") (pinfunction "OUT_1") (pintype "output"))
      (node (ref "U2") (pin "2") (pinfunction "IN-_2") (pintype "input"))
    )
    (net (code "21") (name "CH13_CV") (class "Default")
      (node (ref "R38") (pin "2") (pinfunction "2_2") (pintype "passive"))
      (node (ref "TP_5") (pin "TP") (pinfunction "TP_TP") (pintype "input"))
      (node (ref "U2") (pin "6") (pinfunction "IN-_6") (pintype "input"))
      (node (ref "U2") (pin "7") (pinfunction "OUT_7") (pintype "output"))
    )
    (net (code "22") (name "CH14_CV") (class "Default")
      (node (ref "R24") (pin "1") (pinfunction "1_1") (pintype "passive"))
      (node (ref "TP_6") (pin "TP") (pinfunction "TP_TP") (pintype "input"))
      (node (ref "U2") (pin "8") (pinfunction "OUT_8") (pintype "output"))
      (node (ref "U2") (pin "9") (pinfunction "IN-_9") (pintype "input"))
    )
    (net (code "23") (name "CH15_CV") (class "Default")
      (node (ref "R25") (pin "1") (pinfunction "1_1") (pintype "passive"))
      (node (ref "TP_7") (pin "TP") (pinfunction "TP_TP") (pintype "input"))
      (node (ref "U2") (pin "13") (pinfunction "IN-_13") (pintype "input"))
      (node (ref "U2") (pin "14") (pinfunction "OUT_14") (pintype "output"))
    )
    (net (code "24") (name "DVCC") (class "Default")
      (node (ref "FB2") (pin "1") (pinfunction "1_1") (pintype "bidirectional"))
      (node (ref "H1") (pin "5") (pinfunction "5_5") (pintype "passive"))
      (node (ref "H1") (pin "6") (pinfunction "6_6") (pintype "passive"))
    )
    (net (code "25") (name "D_VIN") (class "Default")
      (node (ref "C2") (pin "+") (pinfunction "+_+") (pintype "passive"))
      (node (ref "C27") (pin "1") (pinfunction "1_1") (pintype "passive"))
      (node (ref "C28") (pin "1") (pinfunction "1_1") (pintype "passive"))
      (node (ref "FB2") (pin "2") (pinfunction "2_2") (pintype "bidirectional"))
      (node (ref "U4") (pin "3") (pinfunction "OUT_3") (pintype "passive"))
    )
    (net (code "26") (name "GND") (class "Default")
      (node (ref "C1") (pin "-") (pinfunction "-_-") (pintype "passive"))
      (node (ref "C10") (pin "2") (pinfunction "2_2") (pintype "passive"))
      (node (ref "C11") (pin "2") (pinfunction "2_2") (pintype "passive"))
      (node (ref "C12") (pin "2") (pinfunction "2_2") (pintype "passive"))
      (node (ref "C14") (pin "2") (pinfunction "2_2") (pintype "passive"))
      (node (ref "C15") (pin "2") (pinfunction "2_2") (pintype "passive"))
      (node (ref "C16") (pin "1") (pinfunction "1_1") (pintype "passive"))
      (node (ref "C17") (pin "2") (pinfunction "2_2") (pintype "passive"))
      (node (ref "C18") (pin "1") (pinfunction "1_1") (pintype "passive"))
      (node (ref "C19") (pin "2") (pinfunction "2_2") (pintype "passive"))
      (node (ref "C2") (pin "-") (pinfunction "-_-") (pintype "passive"))
      (node (ref "C20") (pin "2") (pinfunction "2_2") (pintype "passive"))
      (node (ref "C21") (pin "2") (pinfunction "2_2") (pintype "passive"))
      (node (ref "C22") (pin "2") (pinfunction "2_2") (pintype "passive"))
      (node (ref "C23") (pin "2") (pinfunction "2_2") (pintype "passive"))
      (node (ref "C24") (pin "2") (pinfunction "2_2") (pintype "passive"))
      (node (ref "C25") (pin "2") (pinfunction "2_2") (pintype "passive"))
      (node (ref "C26") (pin "2") (pinfunction "2_2") (pintype "passive"))
      (node (ref "C27") (pin "2") (pinfunction "2_2") (pintype "passive"))
      (node (ref "C28") (pin "2") (pinfunction "2_2") (pintype "passive"))
      (node (ref "C29") (pin "2") (pinfunction "2_2") (pintype "passive"))
      (node (ref "C3") (pin "2") (pinfunction "2_2") (pintype "passive"))
      (node (ref "C30") (pin "2") (pinfunction "2_2") (pintype "passive"))
      (node (ref "C31") (pin "2") (pinfunction "2_2") (pintype "passive"))
      (node (ref "C32") (pin "2") (pinfunction "2_2") (pintype "passive"))
      (node (ref "C33") (pin "2") (pinfunction "2_2") (pintype "passive"))
      (node (ref "C34") (pin "2") (pinfunction "2_2") (pintype "passive"))
      (node (ref "C35") (pin "2") (pinfunction "2_2") (pintype "passive"))
      (node (ref "C36") (pin "1") (pinfunction "1_1") (pintype "passive"))
      (node (ref "C37") (pin "1") (pinfunction "1_1") (pintype "passive"))
      (node (ref "C4") (pin "2") (pinfunction "2_2") (pintype "passive"))
      (node (ref "C5") (pin "2") (pinfunction "2_2") (pintype "passive"))
      (node (ref "C6") (pin "2") (pinfunction "2_2") (pintype "passive"))
      (node (ref "C7") (pin "2") (pinfunction "2_2") (pintype "passive"))
      (node (ref "C8") (pin "2") (pinfunction "2_2") (pintype "passive"))
      (node (ref "C9") (pin "2") (pinfunction "2_2") (pintype "passive"))
      (node (ref "H1") (pin "3") (pinfunction "3_3") (pintype "passive"))
      (node (ref "H1") (pin "4") (pinfunction "4_4") (pintype "passive"))
      (node (ref "H1") (pin "7") (pinfunction "7_7") (pintype "passive"))
      (node (ref "H1") (pin "8") (pinfunction "8_8") (pintype "passive"))
      (node (ref "H4") (pin "1") (pinfunction "1_1") (pintype "passive"))
      (node (ref "H4") (pin "3") (pinfunction "3_3") (pintype "passive"))
      (node (ref "H4") (pin "5") (pinfunction "5_5") (pintype "passive"))
      (node (ref "H4") (pin "7") (pinfunction "7_7") (pintype "passive"))
      (node (ref "H5") (pin "1") (pinfunction "1_1") (pintype "passive"))
      (node (ref "H5") (pin "3") (pinfunction "3_3") (pintype "passive"))
      (node (ref "H5") (pin "5") (pinfunction "5_5") (pintype "passive"))
      (node (ref "H5") (pin "7") (pinfunction "7_7") (pintype "passive"))
      (node (ref "H7") (pin "7") (pinfunction "7_7") (pintype "passive"))
      (node (ref "H7") (pin "8") (pinfunction "8_8") (pintype "passive"))
      (node (ref "H8") (pin "4") (pinfunction "4_4") (pintype "passive"))
      (node (ref "MIDI1") (pin "2") (pinfunction "2_2") (pintype "passive"))
      (node (ref "MIDI1") (pin "G1") (pinfunction "G1_G1") (pintype "bidirectional"))
      (node (ref "MIDI1") (pin "G2") (pinfunction "G2_G2") (pintype "bidirectional"))
      (node (ref "R1") (pin "1") (pinfunction "1_1") (pintype "passive"))
      (node (ref "R13") (pin "1") (pinfunction "1_1") (pintype "passive"))
      (node (ref "R14") (pin "1") (pinfunction "1_1") (pintype "passive"))
      (node (ref "R15") (pin "1") (pinfunction "1_1") (pintype "passive"))
      (node (ref "R16") (pin "1") (pinfunction "1_1") (pintype "passive"))
      (node (ref "R17") (pin "1") (pinfunction "1_1") (pintype "passive"))
      (node (ref "R18") (pin "1") (pinfunction "1_1") (pintype "passive"))
      (node (ref "R2") (pin "1") (pinfunction "1_1") (pintype "passive"))
      (node (ref "R21") (pin "2") (pinfunction "2_2") (pintype "passive"))
      (node (ref "R27") (pin "2") (pinfunction "2_2") (pintype "passive"))
      (node (ref "R28") (pin "2") (pinfunction "2_2") (pintype "passive"))
      (node (ref "R29") (pin "2") (pinfunction "2_2") (pintype "passive"))
      (node (ref "R3") (pin "1") (pinfunction "1_1") (pintype "passive"))
      (node (ref "R35") (pin "2") (pinfunction "2_2") (pintype "passive"))
      (node (ref "R36") (pin "2") (pinfunction "2_2") (pintype "passive"))
      (node (ref "R37") (pin "2") (pinfunction "2_2") (pintype "passive"))
      (node (ref "R4") (pin "1") (pinfunction "1_1") (pintype "passive"))
      (node (ref "R5") (pin "1") (pinfunction "1_1") (pintype "passive"))
      (node (ref "R6") (pin "1") (pinfunction "1_1") (pintype "passive"))
      (node (ref "T1") (pin "2") (pinfunction "E_2") (pintype "passive"))
      (node (ref "T2") (pin "2") (pinfunction "E_2") (pintype "passive"))
      (node (ref "U$1") (pin "P$1") (pinfunction "14_P$1") (pintype "bidirectional"))
      (node (ref "U$1") (pin "P$2") (pinfunction "15_P$2") (pintype "bidirectional"))
      (node (ref "U1") (pin "4") (pinfunction "V-_4") (pintype "power_in"))
      (node (ref "U2") (pin "11") (pinfunction "V-_11") (pintype "power_in"))
      (node (ref "U4") (pin "2") (pinfunction "GND_2") (pintype "input"))
      (node (ref "U4") (pin "2@1") (pinfunction "GND1_2@1") (pintype "input"))
      (node (ref "U5") (pin "2") (pinfunction "GND_2") (pintype "power_in"))
      (node (ref "U6B") (pin "27") (pinfunction "AVSS_27") (pintype "bidirectional"))
      (node (ref "U6B") (pin "28") (pinfunction "DVSS_28") (pintype "power_in"))
      (node (ref "X1") (pin "GND@0") (pinfunction "0_GND@0") (pintype "passive"))
    )
    (net (code "27") (name "MONO_GK") (class "Default")
      (node (ref "H2") (pin "7") (pinfunction "7_7") (pintype "passive"))
      (node (ref "R19") (pin "1") (pinfunction "1_1") (pintype "passive"))
    )
    (net (code "28") (name "Net-(C13-Pad2)") (class "Default")
      (node (ref "C13") (pin "2") (pinfunction "2_2") (pintype "passive"))
      (node (ref "R19") (pin "2") (pinfunction "2_2") (pintype "passive"))
    )
    (net (code "29") (name "Net-(D1-AK)") (class "Default")
      (node (ref "D1") (pin "3") (pinfunction "AK_3") (pintype "passive"))
      (node (ref "R22") (pin "2") (pinfunction "2_2") (pintype "passive"))
      (node (ref "U3") (pin "1") (pinfunction "OUT_1") (pintype "output"))
      (node (ref "U3") (pin "2") (pinfunction "IN-_2") (pintype "input"))
    )
    (net (code "30") (name "Net-(D2-AK)") (class "Default")
      (node (ref "D2") (pin "3") (pinfunction "AK_3") (pintype "passive"))
      (node (ref "R23") (pin "1") (pinfunction "1_1") (pintype "passive"))
      (node (ref "U3") (pin "6") (pinfunction "IN-_6") (pintype "input"))
      (node (ref "U3") (pin "7") (pinfunction "OUT_7") (pintype "output"))
    )
    (net (code "31") (name "Net-(H2-Pad8)") (class "Default")
      (node (ref "H2") (pin "8") (pinfunction "8_8") (pintype "passive"))
      (node (ref "JP2") (pin "2") (pinfunction "2_2") (pintype "passive"))
    )
    (net (code "32") (name "Net-(H3-Pad1)") (class "Default")
      (node (ref "H3") (pin "1") (pinfunction "1_1") (pintype "passive"))
      (node (ref "JP3") (pin "2") (pinfunction "2_2") (pintype "passive"))
    )
    (net (code "33") (name "Net-(H3-Pad3)") (class "Default")
      (node (ref "H3") (pin "3") (pinfunction "3_3") (pintype "passive"))
      (node (ref "JP1") (pin "2") (pinfunction "2_2") (pintype "passive"))
    )
    (net (code "34") (name "Net-(MIDI1-Pad4)") (class "Default")
      (node (ref "MIDI1") (pin "4") (pinfunction "4_4") (pintype "passive"))
      (node (ref "R30") (pin "2") (pinfunction "2_2") (pintype "passive"))
    )
    (net (code "35") (name "Net-(MIDI1-Pad5)") (class "Default")
      (node (ref "MIDI1") (pin "5") (pinfunction "5_5") (pintype "passive"))
      (node (ref "R31") (pin "2") (pinfunction "2_2") (pintype "passive"))
    )
    (net (code "36") (name "Net-(R10-Pad1)") (class "Default")
      (node (ref "R10") (pin "1") (pinfunction "1_1") (pintype "passive"))
      (node (ref "R16") (pin "2") (pinfunction "2_2") (pintype "passive"))
      (node (ref "U$1") (pin "4") (pinfunction "4_4") (pintype "bidirectional"))
    )
    (net (code "37") (name "Net-(R11-Pad1)") (class "Default")
      (node (ref "R11") (pin "1") (pinfunction "1_1") (pintype "passive"))
      (node (ref "R17") (pin "2") (pinfunction "2_2") (pintype "passive"))
      (node (ref "U$1") (pin "5") (pinfunction "5_5") (pintype "bidirectional"))
    )
    (net (code "38") (name "Net-(R12-Pad1)") (class "Default")
      (node (ref "R12") (pin "1") (pinfunction "1_1") (pintype "passive"))
      (node (ref "R18") (pin "2") (pinfunction "2_2") (pintype "passive"))
      (node (ref "U$1") (pin "6") (pinfunction "6_6") (pintype "bidirectional"))
    )
    (net (code "39") (name "Net-(R13-Pad2)") (class "Default")
      (node (ref "R13") (pin "2") (pinfunction "2_2") (pintype "passive"))
      (node (ref "R7") (pin "1") (pinfunction "1_1") (pintype "passive"))
      (node (ref "U$1") (pin "1") (pinfunction "1_1") (pintype "bidirectional"))
    )
    (net (code "40") (name "Net-(R14-Pad2)") (class "Default")
      (node (ref "R14") (pin "2") (pinfunction "2_2") (pintype "passive"))
      (node (ref "R8") (pin "1") (pinfunction "1_1") (pintype "passive"))
      (node (ref "U$1") (pin "2") (pinfunction "2_2") (pintype "bidirectional"))
    )
    (net (code "41") (name "Net-(R15-Pad2)") (class "Default")
      (node (ref "R15") (pin "2") (pinfunction "2_2") (pintype "passive"))
      (node (ref "R9") (pin "1") (pinfunction "1_1") (pintype "passive"))
      (node (ref "U$1") (pin "3") (pinfunction "3_3") (pintype "bidirectional"))
    )
    (net (code "42") (name "Net-(R22-Pad1)") (class "Default")
      (node (ref "R22") (pin "1") (pinfunction "1_1") (pintype "passive"))
      (node (ref "U$1") (pin "7") (pinfunction "7_7") (pintype "bidirectional"))
    )
    (net (code "43") (name "Net-(R23-Pad2)") (class "Default")
      (node (ref "R23") (pin "2") (pinfunction "2_2") (pintype "passive"))
      (node (ref "U$1") (pin "8") (pinfunction "8_8") (pintype "bidirectional"))
    )
    (net (code "44") (name "Net-(T1-B)") (class "Default")
      (node (ref "R32") (pin "2") (pinfunction "2_2") (pintype "passive"))
      (node (ref "T1") (pin "1") (pinfunction "B_1") (pintype "passive"))
    )
    (net (code "45") (name "Net-(T1-C)") (class "Default")
      (node (ref "R31") (pin "1") (pinfunction "1_1") (pintype "passive"))
      (node (ref "T1") (pin "3") (pinfunction "C_3") (pintype "passive"))
    )
    (net (code "46") (name "Net-(T2-B)") (class "Default")
      (node (ref "R34") (pin "2") (pinfunction "2_2") (pintype "passive"))
      (node (ref "T2") (pin "1") (pinfunction "B_1") (pintype "passive"))
    )
    (net (code "47") (name "Net-(T2-C)") (class "Default")
      (node (ref "R32") (pin "1") (pinfunction "1_1") (pintype "passive"))
      (node (ref "R33") (pin "1") (pinfunction "1_1") (pintype "passive"))
      (node (ref "T2") (pin "3") (pinfunction "C_3") (pintype "passive"))
    )
    (net (code "48") (name "Net-(U1A-IN+)") (class "Default")
      (node (ref "C3") (pin "1") (pinfunction "1_1") (pintype "passive"))
      (node (ref "JP1") (pin "3") (pinfunction "3_3") (pintype "passive"))
      (node (ref "R1") (pin "2") (pinfunction "2_2") (pintype "passive"))
      (node (ref "U1") (pin "3") (pinfunction "IN+_3") (pintype "input"))
    )
    (net (code "49") (name "Net-(U1B-IN+)") (class "Default")
      (node (ref "C4") (pin "1") (pinfunction "1_1") (pintype "passive"))
      (node (ref "H3") (pin "4") (pinfunction "4_4") (pintype "passive"))
      (node (ref "R2") (pin "2") (pinfunction "2_2") (pintype "passive"))
      (node (ref "U1") (pin "5") (pinfunction "IN+_5") (pintype "input"))
    )
    (net (code "50") (name "Net-(U2A-IN+)") (class "Default")
      (node (ref "C5") (pin "1") (pinfunction "1_1") (pintype "passive"))
      (node (ref "H3") (pin "5") (pinfunction "5_5") (pintype "passive"))
      (node (ref "R3") (pin "2") (pinfunction "2_2") (pintype "passive"))
      (node (ref "U2") (pin "3") (pinfunction "IN+_3") (pintype "input"))
    )
    (net (code "51") (name "Net-(U2B-IN+)") (class "Default")
      (node (ref "C6") (pin "1") (pinfunction "1_1") (pintype "passive"))
      (node (ref "H3") (pin "6") (pinfunction "6_6") (pintype "passive"))
      (node (ref "R4") (pin "2") (pinfunction "2_2") (pintype "passive"))
      (node (ref "U2") (pin "5") (pinfunction "IN+_5") (pintype "input"))
    )
    (net (code "52") (name "Net-(U2C-IN+)") (class "Default")
      (node (ref "C7") (pin "1") (pinfunction "1_1") (pintype "passive"))
      (node (ref "H3") (pin "7") (pinfunction "7_7") (pintype "passive"))
      (node (ref "R5") (pin "2") (pinfunction "2_2") (pintype "passive"))
      (node (ref "U2") (pin "10") (pinfunction "IN+_10") (pintype "input"))
    )
    (net (code "53") (name "Net-(U2D-IN+)") (class "Default")
      (node (ref "C8") (pin "1") (pinfunction "1_1") (pintype "passive"))
      (node (ref "H3") (pin "8") (pinfunction "8_8") (pintype "passive"))
      (node (ref "R6") (pin "2") (pinfunction "2_2") (pintype "passive"))
      (node (ref "U2") (pin "12") (pinfunction "IN+_12") (pintype "input"))
    )
    (net (code "54") (name "Net-(U3A-IN+)") (class "Default")
      (node (ref "C13") (pin "1") (pinfunction "1_1") (pintype "passive"))
      (node (ref "R21") (pin "1") (pinfunction "1_1") (pintype "passive"))
      (node (ref "TP3") (pin "TP") (pinfunction "TP_TP") (pintype "input"))
      (node (ref "U3") (pin "3") (pinfunction "IN+_3") (pintype "input"))
    )
    (net (code "55") (name "Net-(U3B-IN+)") (class "Default")
      (node (ref "C14") (pin "1") (pinfunction "1_1") (pintype "passive"))
      (node (ref "R20") (pin "2") (pinfunction "2_2") (pintype "passive"))
      (node (ref "TP2") (pin "TP") (pinfunction "TP_TP") (pintype "input"))
      (node (ref "U3") (pin "5") (pinfunction "IN+_5") (pintype "input"))
    )
    (net (code "56") (name "P1.0") (class "Default")
      (node (ref "C21") (pin "1") (pinfunction "1_1") (pintype "passive"))
      (node (ref "R26") (pin "2") (pinfunction "2_2") (pintype "passive"))
      (node (ref "R29") (pin "1") (pinfunction "1_1") (pintype "passive"))
      (node (ref "U6B") (pin "31") (pinfunction "P1.0_31") (pintype "bidirectional"))
    )
    (net (code "57") (name "P1.1") (class "Default")
      (node (ref "H6") (pin "1") (pinfunction "1_1") (pintype "passive"))
      (node (ref "U6B") (pin "1") (pinfunction "P1.1_1") (pintype "bidirectional"))
    )
    (net (code "58") (name "P1.2") (class "Default")
      (node (ref "R34") (pin "1") (pinfunction "1_1") (pintype "passive"))
      (node (ref "TP_SER") (pin "TP") (pinfunction "TP_TP") (pintype "input"))
      (node (ref "U6B") (pin "2") (pinfunction "P1.2_2") (pintype "bidirectional"))
    )
    (net (code "59") (name "P1.3") (class "Default")
      (node (ref "C26") (pin "1") (pinfunction "1_1") (pintype "passive"))
      (node (ref "R37") (pin "1") (pinfunction "1_1") (pintype "passive"))
      (node (ref "R40") (pin "1") (pinfunction "1_1") (pintype "passive"))
      (node (ref "U6B") (pin "3") (pinfunction "P1.3_3") (pintype "bidirectional"))
    )
    (net (code "60") (name "P1.4") (class "Default")
      (node (ref "C25") (pin "1") (pinfunction "1_1") (pintype "passive"))
      (node (ref "R36") (pin "1") (pinfunction "1_1") (pintype "passive"))
      (node (ref "R39") (pin "1") (pinfunction "1_1") (pintype "passive"))
      (node (ref "U6B") (pin "4") (pinfunction "P1.4_4") (pintype "bidirectional"))
    )
    (net (code "61") (name "P1.5") (class "Default")
      (node (ref "C24") (pin "1") (pinfunction "1_1") (pintype "passive"))
      (node (ref "R35") (pin "1") (pinfunction "1_1") (pintype "passive"))
      (node (ref "R38") (pin "1") (pinfunction "1_1") (pintype "passive"))
      (node (ref "U6B") (pin "5") (pinfunction "P1.5_5") (pintype "bidirectional"))
    )
    (net (code "62") (name "P1.6") (class "Default")
      (node (ref "C19") (pin "1") (pinfunction "1_1") (pintype "passive"))
      (node (ref "R24") (pin "2") (pinfunction "2_2") (pintype "passive"))
      (node (ref "R27") (pin "1") (pinfunction "1_1") (pintype "passive"))
      (node (ref "U6B") (pin "21") (pinfunction "P1.6_21") (pintype "bidirectional"))
    )
    (net (code "63") (name "P1.7") (class "Default")
      (node (ref "C20") (pin "1") (pinfunction "1_1") (pintype "passive"))
      (node (ref "R25") (pin "2") (pinfunction "2_2") (pintype "passive"))
      (node (ref "R28") (pin "1") (pinfunction "1_1") (pintype "passive"))
      (node (ref "U6B") (pin "22") (pinfunction "P1.7_22") (pintype "bidirectional"))
    )
    (net (code "64") (name "P2.3") (class "Default")
      (node (ref "H7") (pin "1") (pinfunction "1_1") (pintype "passive"))
      (node (ref "U6B") (pin "15") (pinfunction "P2.3_15") (pintype "bidirectional"))
    )
    (net (code "65") (name "P2.4") (class "Default")
      (node (ref "H7") (pin "2") (pinfunction "2_2") (pintype "passive"))
      (node (ref "U6B") (pin "16") (pinfunction "P2.4_16") (pintype "bidirectional"))
    )
    (net (code "66") (name "P2.5") (class "Default")
      (node (ref "H7") (pin "3") (pinfunction "3_3") (pintype "passive"))
      (node (ref "U6B") (pin "17") (pinfunction "P2.5_17") (pintype "input"))
    )
    (net (code "67") (name "P2.6") (class "Default")
      (node (ref "C37") (pin "2") (pinfunction "2_2") (pintype "passive"))
      (node (ref "U6B") (pin "26") (pinfunction "P2.6_26") (pintype "bidirectional"))
      (node (ref "X1") (pin "1") (pinfunction "1_1") (pintype "passive"))
    )
    (net (code "68") (name "P2.7") (class "Default")
      (node (ref "C36") (pin "2") (pinfunction "2_2") (pintype "passive"))
      (node (ref "U6B") (pin "25") (pinfunction "P2.7_25") (pintype "bidirectional"))
      (node (ref "X1") (pin "2") (pinfunction "2_2") (pintype "passive"))
    )
    (net (code "69") (name "P3.0") (class "Default")
      (node (ref "H6") (pin "3") (pinfunction "3_3") (pintype "passive"))
      (node (ref "U6B") (pin "7") (pinfunction "P3.0_7") (pintype "power_in"))
    )
    (net (code "70") (name "P3.1") (class "Default")
      (node (ref "H6") (pin "2") (pinfunction "2_2") (pintype "passive"))
      (node (ref "U6B") (pin "6") (pinfunction "P3.1_6") (pintype "power_in"))
    )
    (net (code "71") (name "P3.2") (class "Default")
      (node (ref "H6") (pin "6") (pinfunction "6_6") (pintype "passive"))
      (node (ref "U6B") (pin "12") (pinfunction "P3.2_12") (pintype "power_in"))
    )
    (net (code "72") (name "P3.3") (class "Default")
      (node (ref "H6") (pin "7") (pinfunction "7_7") (pintype "passive"))
      (node (ref "U6B") (pin "13") (pinfunction "P3.3_13") (pintype "bidirectional"))
    )
    (net (code "73") (name "P3.4") (class "Default")
      (node (ref "H6") (pin "8") (pinfunction "8_8") (pintype "passive"))
      (node (ref "U6B") (pin "14") (pinfunction "P3.4_14") (pintype "bidirectional"))
    )
    (net (code "74") (name "P3.5") (class "Default")
      (node (ref "H7") (pin "4") (pinfunction "4_4") (pintype "passive"))
      (node (ref "U6B") (pin "18") (pinfunction "P3.5_18") (pintype "bidirectional"))
    )
    (net (code "75") (name "P3.6") (class "Default")
      (node (ref "H7") (pin "5") (pinfunction "5_5") (pintype "passive"))
      (node (ref "U6B") (pin "19") (pinfunction "P3.6_19") (pintype "bidirectional"))
    )
    (net (code "76") (name "P3.7") (class "Default")
      (node (ref "H7") (pin "6") (pinfunction "6_6") (pintype "passive"))
      (node (ref "U6B") (pin "20") (pinfunction "P3.7_20") (pintype "bidirectional"))
    )
    (net (code "77") (name "TEST") (class "Default")
      (node (ref "H8") (pin "1") (pinfunction "1_1") (pintype "passive"))
      (node (ref "U6B") (pin "24") (pinfunction "TEST_24") (pintype "bidirectional"))
    )
    (net (code "78") (name "VIN") (class "Default")
      (node (ref "C1") (pin "+") (pinfunction "+_+") (pintype "passive"))
      (node (ref "C10") (pin "1") (pinfunction "1_1") (pintype "passive"))
      (node (ref "C11") (pin "1") (pinfunction "1_1") (pintype "passive"))
      (node (ref "C12") (pin "1") (pinfunction "1_1") (pintype "passive"))
      (node (ref "C9") (pin "1") (pinfunction "1_1") (pintype "passive"))
      (node (ref "FB1") (pin "2") (pinfunction "2_2") (pintype "bidirectional"))
      (node (ref "U1") (pin "8") (pinfunction "V+_8") (pintype "power_in"))
      (node (ref "U2") (pin "4") (pinfunction "V+_4") (pintype "power_in"))
    )
    (net (code "79") (name "unconnected-(MIDI1-Pad1)") (class "Default")
      (node (ref "MIDI1") (pin "1") (pinfunction "1_1") (pintype "passive"))
    )
    (net (code "80") (name "unconnected-(MIDI1-Pad3)") (class "Default")
      (node (ref "MIDI1") (pin "3") (pinfunction "3_3") (pintype "passive"))
    )
    (net (code "81") (name "unconnected-(U$1-Pad9)") (class "Default")
      (node (ref "U$1") (pin "9") (pinfunction "9_9") (pintype "bidirectional"))
    )
    (net (code "82") (name "unconnected-(U5-ADJ-Pad4)") (class "Default")
      (node (ref "U5") (pin "4") (pinfunction "ADJ_4") (pintype "passive"))
    )
    (net (code "83") (name "unconnected-(U6B-NC_1-Pad8)") (class "Default")
      (node (ref "U6B") (pin "8") (pinfunction "NC_1_8") (pintype "bidirectional"))
    )
    (net (code "84") (name "unconnected-(U6B-NC_2-Pad32)") (class "Default")
      (node (ref "U6B") (pin "32") (pinfunction "NC_2_32") (pintype "power_in"))
    )
    (net (code "85") (name "~{RST}") (class "Default")
      (node (ref "C35") (pin "1") (pinfunction "1_1") (pintype "passive"))
      (node (ref "H8") (pin "2") (pinfunction "2_2") (pintype "passive"))
      (node (ref "R41") (pin "2") (pinfunction "2_2") (pintype "passive"))
      (node (ref "U6B") (pin "23") (pinfunction "RST_23") (pintype "bidirectional"))
    )
  )
)
